# ProDoc_OHPP_003A_MIDI_B.net
KiCad netlist of a schematic drawn in EasyEDA Pro
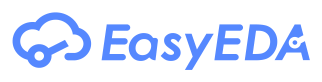
[diagram p0: POWER BLOCK DIAGRAM]
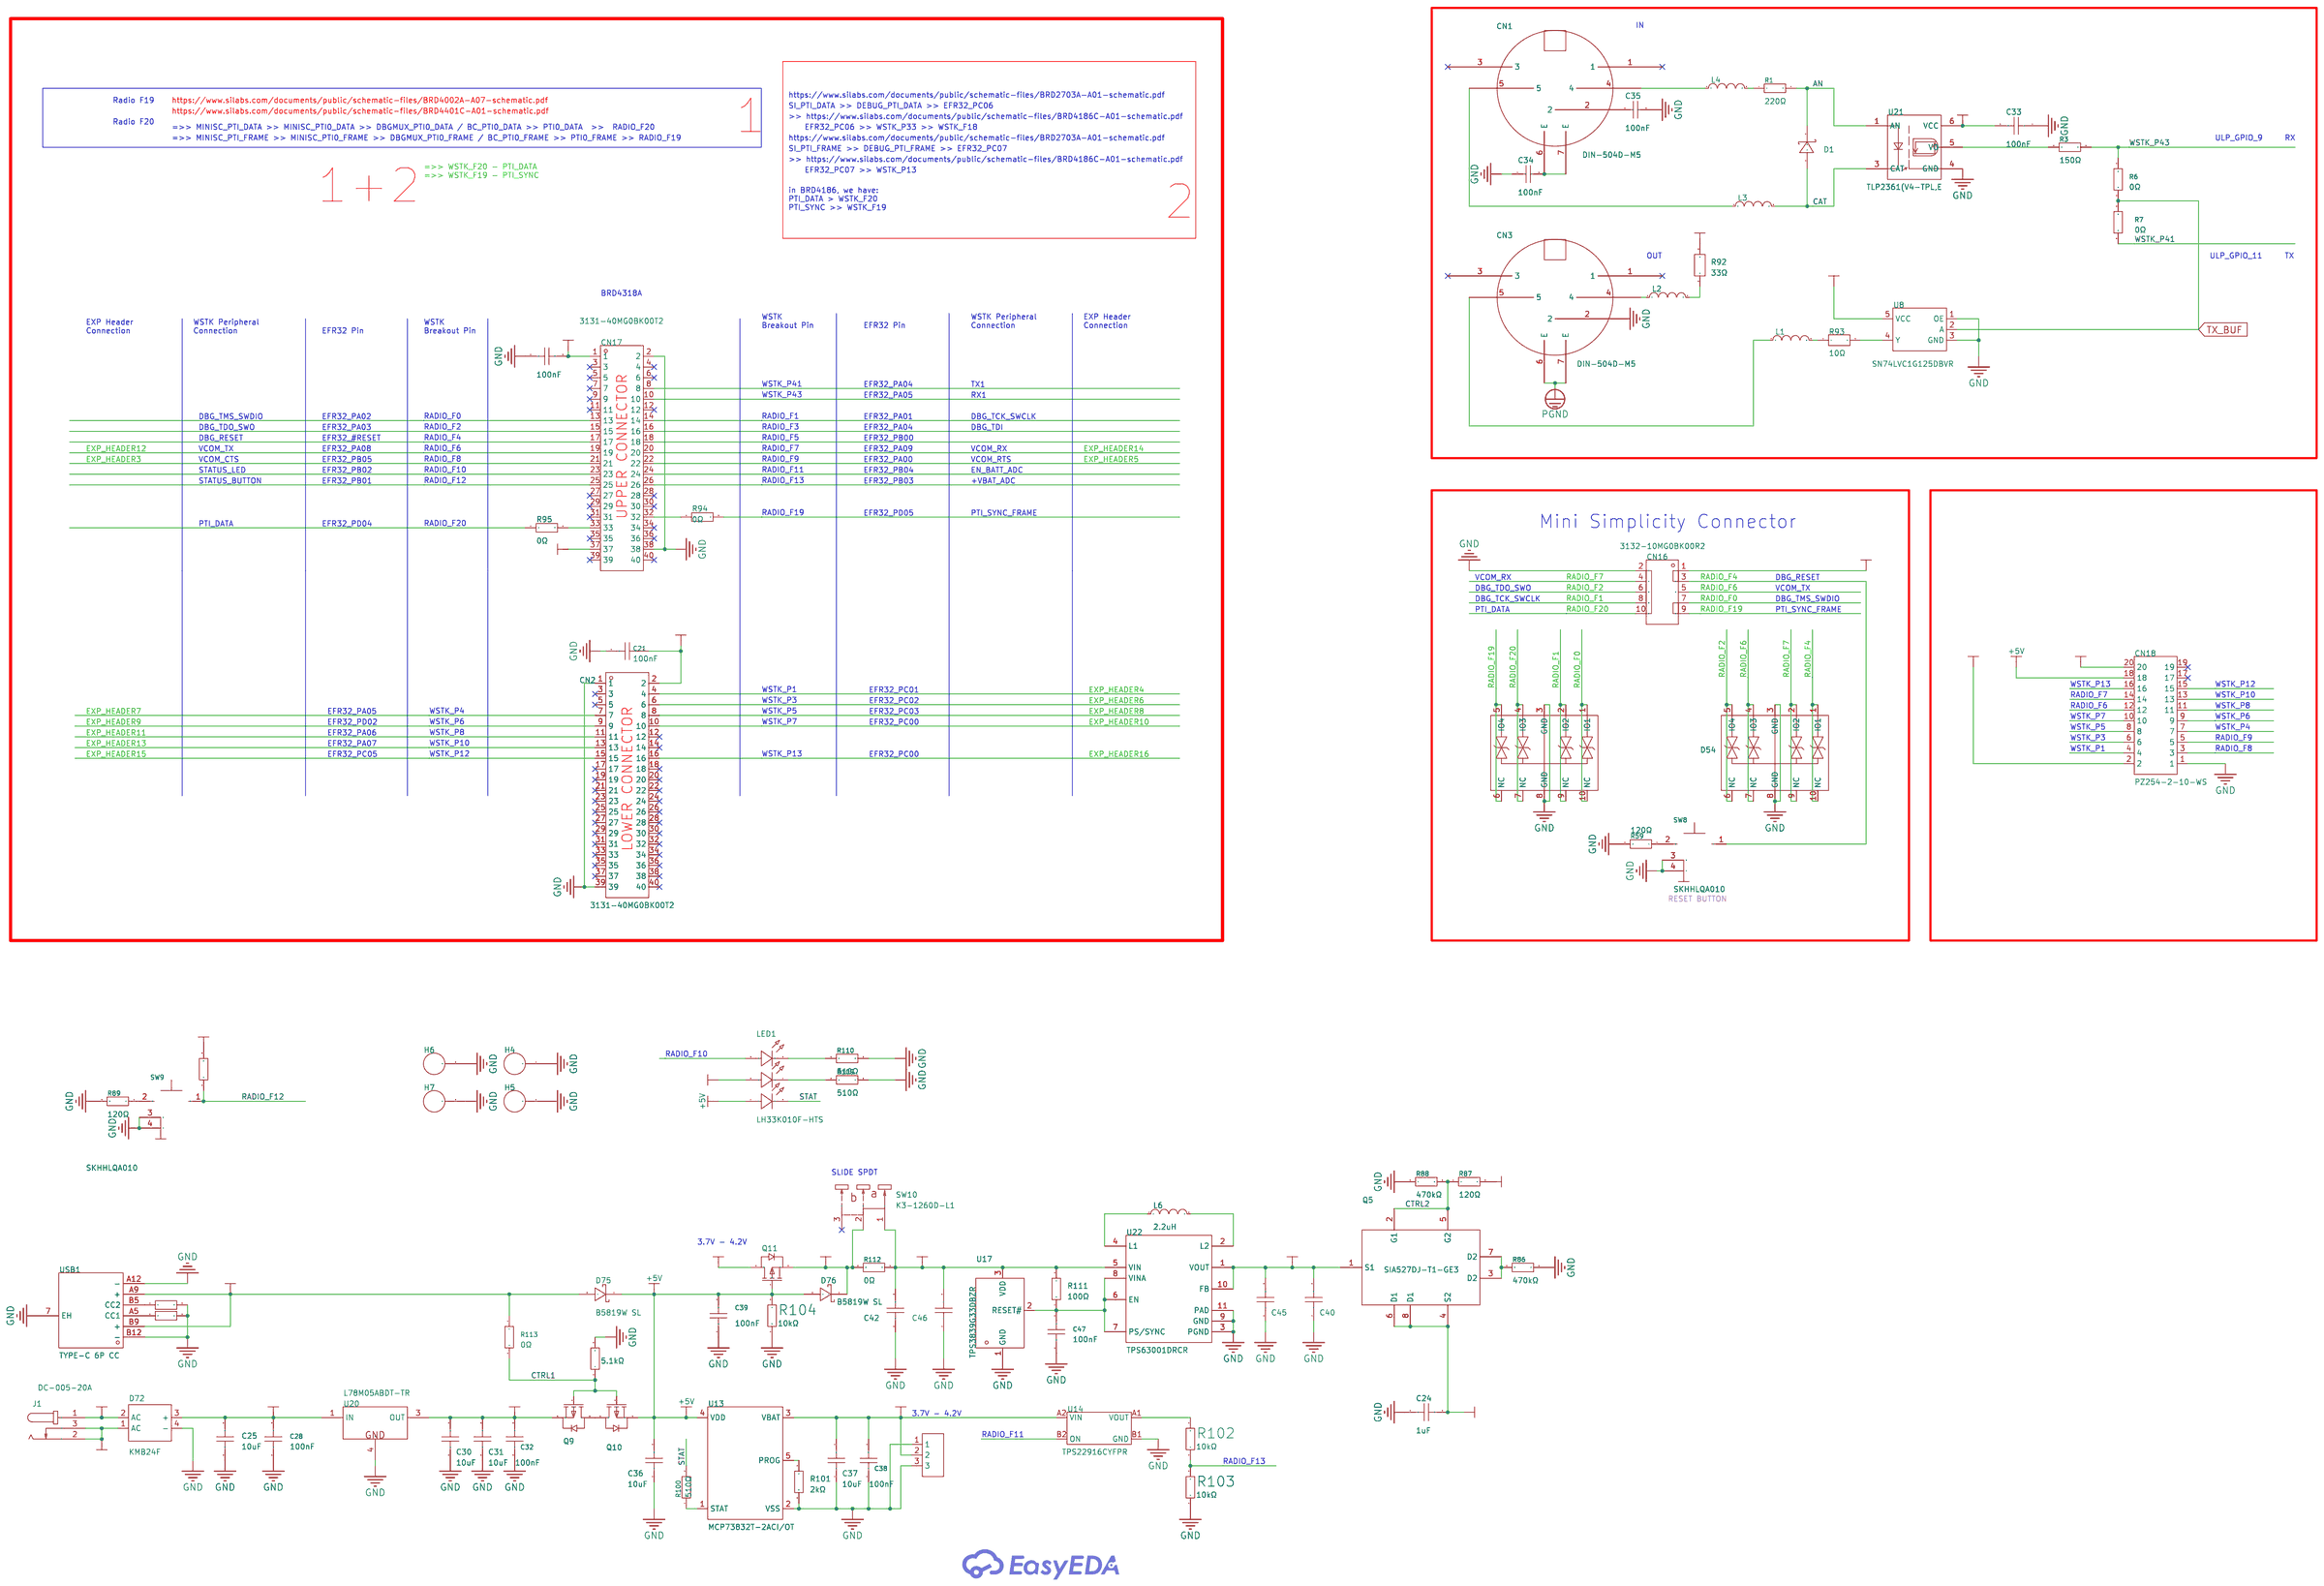
[diagram p1: MIDI]

(export (version "E")
  (design (tool "Eeschema 10.0.6"))
  (components
    (comp (ref "C20")
      (value "100nF")
      (footprint "easyedapro:C0603")
      (fields
        (field (name "Manufacturer Part") "CC0603KRX7R9BB104")
        (field (name "Manufacturer") "YAGEO(国巨)")
      )
      (libsource (lib "easyedapro") (part "CC0603KRX7R9BB104"))
    )
    (comp (ref "C21")
      (value "100nF")
      (footprint "easyedapro:C0603")
      (fields
        (field (name "Manufacturer Part") "CC0603KRX7R9BB104")
        (field (name "Manufacturer") "YAGEO(国巨)")
      )
      (libsource (lib "easyedapro") (part "CC0603KRX7R9BB104"))
    )
    (comp (ref "C24")
      (value "1uF")
      (footprint "easyedapro:C0603")
      (fields
        (field (name "Manufacturer Part") "CL10A105KB8NNNC")
        (field (name "Manufacturer") "SAMSUNG(三星)")
      )
      (libsource (lib "easyedapro") (part "CL10A105KB8NNNC"))
    )
    (comp (ref "C25")
      (value "10uF")
      (description "Capacitance:10uF Tolerance:±20% Tolerance:±20% Voltage Rating:25V Temperature Coefficient:X5R")
      (fields
        (field (name "Manufacturer Part") "CL10A106MA8NRNC")
        (field (name "Manufacturer") "SAMSUNG(三星)")
      )
      (libsource (lib "easyedapro") (part "CL21A106KAYNNNE"))
    )
    (comp (ref "C28")
      (value "100nF")
      (footprint "easyedapro:C0603")
      (fields
        (field (name "Manufacturer Part") "CC0603KRX7R9BB104")
        (field (name "Manufacturer") "YAGEO(国巨)")
      )
      (libsource (lib "easyedapro") (part "CC0603KRX7R9BB104"))
    )
    (comp (ref "C30")
      (value "10uF")
      (description "Capacitance:10uF Tolerance:±20% Tolerance:±20% Voltage Rating:25V Temperature Coefficient:X5R")
      (fields
        (field (name "Manufacturer Part") "CL10A106MA8NRNC")
        (field (name "Manufacturer") "SAMSUNG(三星)")
      )
      (libsource (lib "easyedapro") (part "CL21A106KAYNNNE"))
    )
    (comp (ref "C31")
      (value "10uF")
      (description "Capacitance:10uF Tolerance:±20% Tolerance:±20% Voltage Rating:25V Temperature Coefficient:X5R")
      (fields
        (field (name "Manufacturer Part") "CL10A106MA8NRNC")
        (field (name "Manufacturer") "SAMSUNG(三星)")
      )
      (libsource (lib "easyedapro") (part "CL21A106KAYNNNE"))
    )
    (comp (ref "C32")
      (value "100nF")
      (footprint "easyedapro:C0603")
      (fields
        (field (name "Manufacturer Part") "CC0603KRX7R9BB104")
        (field (name "Manufacturer") "YAGEO(国巨)")
      )
      (libsource (lib "easyedapro") (part "CC0603KRX7R9BB104"))
    )
    (comp (ref "C33")
      (value "100nF")
      (footprint "easyedapro:C0603")
      (fields
        (field (name "Manufacturer Part") "CC0603KRX7R9BB104")
        (field (name "Manufacturer") "YAGEO(国巨)")
      )
      (libsource (lib "easyedapro") (part "CC0603KRX7R9BB104"))
    )
    (comp (ref "C34")
      (value "100nF")
      (footprint "easyedapro:C0805")
      (fields
        (field (name "Manufacturer Part") "CL21B104KCFNNNE")
        (field (name "Manufacturer") "SAMSUNG(三星)")
      )
      (libsource (lib "easyedapro") (part "CL21B104KCFNNNE"))
    )
    (comp (ref "C35")
      (value "100nF")
      (footprint "easyedapro:C0805")
      (fields
        (field (name "Manufacturer Part") "CL21B104KCFNNNE")
        (field (name "Manufacturer") "SAMSUNG(三星)")
      )
      (libsource (lib "easyedapro") (part "CL21B104KCFNNNE"))
    )
    (comp (ref "C36")
      (value "10uF")
      (description "Capacitance:10uF Tolerance:±20% Tolerance:±20% Voltage Rating:25V Temperature Coefficient:X5R")
      (fields
        (field (name "Manufacturer Part") "CL10A106MA8NRNC")
        (field (name "Manufacturer") "SAMSUNG(三星)")
      )
      (libsource (lib "easyedapro") (part "CL21A106KAYNNNE"))
    )
    (comp (ref "C37")
      (value "10uF")
      (description "Capacitance:10uF Tolerance:±20% Tolerance:±20% Voltage Rating:25V Temperature Coefficient:X5R")
      (fields
        (field (name "Manufacturer Part") "CL10A106MA8NRNC")
        (field (name "Manufacturer") "SAMSUNG(三星)")
      )
      (libsource (lib "easyedapro") (part "CL21A106KAYNNNE"))
    )
    (comp (ref "C38")
      (value "100nF")
      (footprint "easyedapro:C0603")
      (fields
        (field (name "Manufacturer Part") "CC0603KRX7R9BB104")
        (field (name "Manufacturer") "YAGEO(国巨)")
      )
      (libsource (lib "easyedapro") (part "CC0603KRX7R9BB104"))
    )
    (comp (ref "C39")
      (value "100nF")
      (footprint "easyedapro:C0603")
      (fields
        (field (name "Manufacturer Part") "CC0603KRX7R9BB104")
        (field (name "Manufacturer") "YAGEO(国巨)")
      )
      (libsource (lib "easyedapro") (part "CC0603KRX7R9BB104"))
    )
    (comp (ref "C40")
      (value "10uF")
      (footprint "easyedapro:C0603")
      (description "Capacitance:10uF Tolerance:±20% Tolerance:±20% Voltage Rating:25V Temperature Coefficient:X5R")
      (fields
        (field (name "Manufacturer Part") "CL10A106MA8NRNC")
        (field (name "Manufacturer") "SAMSUNG(三星)")
      )
      (libsource (lib "easyedapro") (part "CL10A106MA8NRNC"))
    )
    (comp (ref "C42")
      (value "10uF")
      (footprint "easyedapro:C0603")
      (description "Capacitance:10uF Tolerance:±20% Tolerance:±20% Voltage Rating:25V Temperature Coefficient:X5R")
      (fields
        (field (name "Manufacturer Part") "CL10A106MA8NRNC")
        (field (name "Manufacturer") "SAMSUNG(三星)")
      )
      (libsource (lib "easyedapro") (part "CL10A106MA8NRNC"))
    )
    (comp (ref "C45")
      (value "10uF")
      (footprint "easyedapro:C0603")
      (description "Capacitance:10uF Tolerance:±20% Tolerance:±20% Voltage Rating:25V Temperature Coefficient:X5R")
      (fields
        (field (name "Manufacturer Part") "CL10A106MA8NRNC")
        (field (name "Manufacturer") "SAMSUNG(三星)")
      )
      (libsource (lib "easyedapro") (part "CL10A106MA8NRNC"))
    )
    (comp (ref "C46")
      (value "10uF")
      (footprint "easyedapro:C0603")
      (description "Capacitance:10uF Tolerance:±20% Tolerance:±20% Voltage Rating:25V Temperature Coefficient:X5R")
      (fields
        (field (name "Manufacturer Part") "CL10A106MA8NRNC")
        (field (name "Manufacturer") "SAMSUNG(三星)")
      )
      (libsource (lib "easyedapro") (part "CL10A106MA8NRNC"))
    )
    (comp (ref "C47")
      (value "100nF")
      (footprint "easyedapro:C0603")
      (fields
        (field (name "Manufacturer Part") "CC0603KRX7R9BB104")
        (field (name "Manufacturer") "YAGEO(国巨)")
      )
      (libsource (lib "easyedapro") (part "CC0603KRX7R9BB104"))
    )
    (comp (ref "CN1")
      (value "DIN-504D-M5")
      (footprint "easyedapro:CONN-TH_DIN-504D-M5")
      (fields (field (name "Manufacturer") "HOOYA(皓宇电子)"))
      (libsource (lib "easyedapro") (part "DIN-504D-M5-CP-V1.0.0"))
    )
    (comp (ref "CN2")
      (value "3131-40MG0BK00T2")
      (footprint "easyedapro:CONN-SMD_40P-P1.27_WCON_3131-40MG0BK00T2")
      (fields (field (name "Manufacturer") "Wcon(维峰电子)"))
      (libsource (lib "easyedapro") (part "3131-40MG0BK00T2"))
    )
    (comp (ref "CN3")
      (value "DIN-504D-M5")
      (footprint "easyedapro:CONN-TH_DIN-504D-M5")
      (fields (field (name "Manufacturer") "HOOYA(皓宇电子)"))
      (libsource (lib "easyedapro") (part "DIN-504D-M5-CP-V1.0.0"))
    )
    (comp (ref "CN16")
      (value "3132-10MG0BK00R2")
      (footprint "easyedapro:IDC-SMD_3132-10MG0BK00R2")
      (fields (field (name "Manufacturer") "Wcon(维峰电子)"))
      (libsource (lib "easyedapro") (part "3132-10MG0BK00R2"))
    )
    (comp (ref "CN17")
      (value "3131-40MG0BK00T2")
      (footprint "easyedapro:CONN-SMD_40P-P1.27_WCON_3131-40MG0BK00T2")
      (fields (field (name "Manufacturer") "Wcon(维峰电子)"))
      (libsource (lib "easyedapro") (part "3131-40MG0BK00T2-UP-CP-V1.0.0"))
    )
    (comp (ref "CN18")
      (value "PZ254-2-10-WS")
      (footprint "easyedapro:HDR-SMD_20P-P2.54-H-M-R2-C10_L8.5")
      (fields (field (name "Manufacturer") "HCTL(华灿天禄)"))
      (libsource (lib "easyedapro") (part "PZ254-2-10-WS"))
    )
    (comp (ref "D1")
      (value "MBRA140T3G")
      (footprint "easyedapro:SMA_L4.3-W2.6-LS5.2-RD")
      (fields (field (name "Manufacturer") "onsemi(安森美)"))
      (libsource (lib "easyedapro") (part "MBRA140T3G"))
    )
    (comp (ref "D54")
      (value "TPD4E02B04DQAR")
      (footprint "easyedapro:USON-10_L2.5-W1.0-P0.50-BL")
      (fields (field (name "Manufacturer") "TI(德州仪器)"))
      (libsource (lib "easyedapro") (part "TPD4E02B04DQAR"))
    )
    (comp (ref "D69")
      (value "TPD4E02B04DQAR")
      (footprint "easyedapro:USON-10_L2.5-W1.0-P0.50-BL")
      (fields (field (name "Manufacturer") "TI(德州仪器)"))
      (libsource (lib "easyedapro") (part "TPD4E02B04DQAR"))
    )
    (comp (ref "D72")
      (value "KMB24F")
      (footprint "easyedapro:DIO-BG-SMD_MBF-TL")
      (fields (field (name "Manufacturer") "MDD(辰达半导体)"))
      (libsource (lib "easyedapro") (part "KMB24F-CP-V1.0.0"))
    )
    (comp (ref "D75")
      (value "B5819W SL")
      (footprint "easyedapro:SOD-123_L2.7-W1.6-LS3.7-RD-1")
      (fields (field (name "Manufacturer") "CJ(江苏长电/长晶)"))
      (libsource (lib "easyedapro") (part "B5819W_C8598"))
    )
    (comp (ref "D76")
      (value "B5819W SL")
      (footprint "easyedapro:SOD-123_L2.7-W1.6-LS3.7-RD-1")
      (fields (field (name "Manufacturer") "CJ(江苏长电/长晶)"))
      (libsource (lib "easyedapro") (part "B5819W_C8598"))
    )
    (comp (ref "H4")
      (value "~")
      (footprint "easyedapro:HOLE_D3M5_D7M0_PAD_PTH")
      (libsource (lib "easyedapro") (part "HOLE_D3M5_D7M0_PAD_PTH"))
    )
    (comp (ref "H5")
      (value "~")
      (footprint "easyedapro:HOLE_D3M5_D7M0_PAD_PTH")
      (libsource (lib "easyedapro") (part "HOLE_D3M5_D7M0_PAD_PTH"))
    )
    (comp (ref "H6")
      (value "~")
      (footprint "easyedapro:HOLE_D3M5_D7M0_PAD_PTH")
      (libsource (lib "easyedapro") (part "HOLE_D3M5_D7M0_PAD_PTH"))
    )
    (comp (ref "H7")
      (value "~")
      (footprint "easyedapro:HOLE_D3M5_D7M0_PAD_PTH")
      (libsource (lib "easyedapro") (part "HOLE_D3M5_D7M0_PAD_PTH"))
    )
    (comp (ref "H8")
      (value "KH-2.54PH180-1X3P-L11.5")
      (footprint "easyedapro:HDR-TH_3P-P2.54-V-M")
      (fields (field (name "Manufacturer") "kinghelm(金航标)"))
      (libsource (lib "easyedapro") (part "KH-2.54PH180-1X3P-L11.5"))
    )
    (comp (ref "J1")
      (value "DC-005-20A")
      (footprint "easyedapro:DC-IN-TH_DC-005-20A")
      (fields (field (name "Manufacturer") "韩国韩荣"))
      (libsource (lib "easyedapro") (part "DC-005-20A_C136744"))
    )
    (comp (ref "L1")
      (value "MMZ1608Y102BTD25")
      (footprint "easyedapro:L0603")
      (fields (field (name "Manufacturer") "TDK"))
      (libsource (lib "easyedapro") (part "MMZ1608Y102BTD25"))
    )
    (comp (ref "L2")
      (value "MMZ1608Y102BTD25")
      (footprint "easyedapro:L0603")
      (fields (field (name "Manufacturer") "TDK"))
      (libsource (lib "easyedapro") (part "MMZ1608Y102BTD25"))
    )
    (comp (ref "L3")
      (value "MMZ1608Y102BTD25")
      (footprint "easyedapro:L0603")
      (fields (field (name "Manufacturer") "TDK"))
      (libsource (lib "easyedapro") (part "MMZ1608Y102BTD25"))
    )
    (comp (ref "L4")
      (value "MMZ1608Y102BTD25")
      (footprint "easyedapro:L0603")
      (fields (field (name "Manufacturer") "TDK"))
      (libsource (lib "easyedapro") (part "MMZ1608Y102BTD25"))
    )
    (comp (ref "L6")
      (value "2.2uH")
      (footprint "easyedapro:L0806")
      (fields (field (name "Manufacturer Part") "TFM201610GHM-2R2MTAA") (field (name "Manufacturer") "TDK"))
      (libsource (lib "easyedapro") (part "TFM201610GHM-2R2MTAA"))
    )
    (comp (ref "LED1")
      (value "LH33K010F-HTS")
      (footprint "easyedapro:LED-TH_6P-L11.6-W4.4-P2.54_LH33K010F-HTS")
      (description "Lamp Holder Type:-")
      (fields (field (name "Manufacturer") "PARALIGHT(光鼎)"))
      (libsource (lib "easyedapro") (part "LH33K010F-HTS"))
    )
    (comp (ref "Q5")
      (value "SIA527DJ-T1-GE3")
      (footprint "easyedapro:POWERPAK-SC-70-6_L2.0-W2.0-P0.65-BL")
      (fields (field (name "Manufacturer") "VISHAY(威世)"))
      (libsource (lib "easyedapro") (part "SIA527DJ-T1-GE3-CP-V1.0.0"))
    )
    (comp (ref "Q9")
      (value "SI2301CDS-T1-GE3")
      (footprint "easyedapro:SOT-23-3_L3.0-W1.7-P0.95-LS2.9-BR")
      (fields (field (name "Manufacturer") "VISHAY(威世)"))
      (libsource (lib "easyedapro") (part "SI2301CDS-T1-GE3"))
    )
    (comp (ref "Q10")
      (value "SI2301CDS-T1-GE3")
      (footprint "easyedapro:SOT-23-3_L3.0-W1.7-P0.95-LS2.9-BR")
      (fields (field (name "Manufacturer") "VISHAY(威世)"))
      (libsource (lib "easyedapro") (part "SI2301CDS-T1-GE3"))
    )
    (comp (ref "Q11")
      (value "SI2301CDS-T1-GE3")
      (footprint "easyedapro:SOT-23-3_L3.0-W1.7-P0.95-LS2.9-BR")
      (fields (field (name "Manufacturer") "VISHAY(威世)"))
      (libsource (lib "easyedapro") (part "SI2301CDS-T1-GE3"))
    )
    (comp (ref "R1")
      (value "220Ω")
      (footprint "easyedapro:R0603")
      (fields
        (field (name "Manufacturer Part") "0603WAF2200T5E")
        (field (name "Manufacturer") "UNI-ROYAL(厚声)")
      )
      (libsource (lib "easyedapro") (part "0603WAF2200T5E"))
    )
    (comp (ref "R3")
      (value "150Ω")
      (footprint "easyedapro:R0603")
      (fields
        (field (name "Manufacturer Part") "0603WAF1500T5E")
        (field (name "Manufacturer") "UNI-ROYAL(厚声)")
      )
      (libsource (lib "easyedapro") (part "0603WAF1500T5E"))
    )
    (comp (ref "R6")
      (value "0Ω")
      (footprint "easyedapro:R0402")
      (fields
        (field (name "Manufacturer Part") "0402WGF0000TCE")
        (field (name "Manufacturer") "UNI-ROYAL(厚声)")
      )
      (libsource (lib "easyedapro") (part "0402WGF0000TCE"))
    )
    (comp (ref "R7")
      (value "0Ω")
      (footprint "easyedapro:R0402")
      (fields
        (field (name "Manufacturer Part") "0402WGF0000TCE")
        (field (name "Manufacturer") "UNI-ROYAL(厚声)")
      )
      (libsource (lib "easyedapro") (part "0402WGF0000TCE"))
    )
    (comp (ref "R59")
      (value "120Ω")
      (footprint "easyedapro:R0603")
      (fields
        (field (name "Manufacturer Part") "0603WAF1200T5E")
        (field (name "Manufacturer") "UNI-ROYAL(厚声)")
      )
      (libsource (lib "easyedapro") (part "0603WAF1200T5E"))
    )
    (comp (ref "R86")
      (value "470kΩ")
      (footprint "easyedapro:R0603")
      (fields
        (field (name "Manufacturer Part") "0603WAF4703T5E")
        (field (name "Manufacturer") "UNI-ROYAL(厚声)")
      )
      (libsource (lib "easyedapro") (part "0603WAF4703T5E"))
    )
    (comp (ref "R87")
      (value "120Ω")
      (footprint "easyedapro:R0603")
      (fields
        (field (name "Manufacturer Part") "0603WAF1200T5E")
        (field (name "Manufacturer") "UNI-ROYAL(厚声)")
      )
      (libsource (lib "easyedapro") (part "0603WAF1200T5E"))
    )
    (comp (ref "R88")
      (value "470kΩ")
      (footprint "easyedapro:R0603")
      (fields
        (field (name "Manufacturer Part") "0603WAF4703T5E")
        (field (name "Manufacturer") "UNI-ROYAL(厚声)")
      )
      (libsource (lib "easyedapro") (part "0603WAF4703T5E"))
    )
    (comp (ref "R89")
      (value "120Ω")
      (footprint "easyedapro:R0603")
      (fields
        (field (name "Manufacturer Part") "0603WAF1200T5E")
        (field (name "Manufacturer") "UNI-ROYAL(厚声)")
      )
      (libsource (lib "easyedapro") (part "0603WAF1200T5E"))
    )
    (comp (ref "R91")
      (value "10kΩ")
      (footprint "easyedapro:R0603")
      (fields
        (field (name "Manufacturer Part") "0603WAF1002T5E")
        (field (name "Manufacturer") "UNI-ROYAL(厚声)")
      )
      (libsource (lib "easyedapro") (part "0603WAF1002T5E"))
    )
    (comp (ref "R92")
      (value "33Ω")
      (fields
        (field (name "Manufacturer Part") "AS05W2J0330T5E")
        (field (name "Manufacturer") "UNI-ROYAL(厚声)")
      )
      (libsource (lib "easyedapro") (part "CRCW080533R0FKEAHP"))
    )
    (comp (ref "R93")
      (value "10Ω")
      (footprint "easyedapro:R0805")
      (fields (field (name "Manufacturer Part") "AC0805FR-7W10RL") (field (name "Manufacturer") "YAGEO(国巨)"))
      (libsource (lib "easyedapro") (part "AC0805FR-7W10RL"))
    )
    (comp (ref "R94")
      (value "0Ω")
      (footprint "easyedapro:R0603")
      (fields
        (field (name "Manufacturer Part") "0603WAF0000T5E")
        (field (name "Manufacturer") "UNI-ROYAL(厚声)")
      )
      (libsource (lib "easyedapro") (part "0603WAF0000T5E"))
    )
    (comp (ref "R95")
      (value "0Ω")
      (footprint "easyedapro:R0603")
      (fields
        (field (name "Manufacturer Part") "0603WAF0000T5E")
        (field (name "Manufacturer") "UNI-ROYAL(厚声)")
      )
      (libsource (lib "easyedapro") (part "0603WAF0000T5E"))
    )
    (comp (ref "R96")
      (value "5.1kΩ")
      (fields
        (field (name "Manufacturer Part") "0603WAF5101T5E")
        (field (name "Manufacturer") "UNI-ROYAL(厚声)")
      )
      (libsource (lib "easyedapro") (part "0402WGF5101TCE"))
    )
    (comp (ref "R97")
      (value "5.1kΩ")
      (fields
        (field (name "Manufacturer Part") "0603WAF5101T5E")
        (field (name "Manufacturer") "UNI-ROYAL(厚声)")
      )
      (libsource (lib "easyedapro") (part "0402WGF5101TCE"))
    )
    (comp (ref "R98")
      (value "5.1kΩ")
      (fields
        (field (name "Manufacturer Part") "0603WAF5101T5E")
        (field (name "Manufacturer") "UNI-ROYAL(厚声)")
      )
      (libsource (lib "easyedapro") (part "0402WGF5101TCE"))
    )
    (comp (ref "R100")
      (value "510Ω")
      (footprint "easyedapro:R0603")
      (fields
        (field (name "Manufacturer Part") "0603WAF5100T5E")
        (field (name "Manufacturer") "UNI-ROYAL(厚声)")
      )
      (libsource (lib "easyedapro") (part "0603WAF5100T5E"))
    )
    (comp (ref "R101")
      (value "2kΩ")
      (footprint "easyedapro:R0603")
      (fields
        (field (name "Manufacturer Part") "0603WAF2001T5E")
        (field (name "Manufacturer") "UNI-ROYAL(厚声)")
      )
      (libsource (lib "easyedapro") (part "0603WAF2001T5E"))
    )
    (comp (ref "R102")
      (value "10kΩ")
      (footprint "easyedapro:R0603")
      (fields
        (field (name "Manufacturer Part") "0603WAF1002T5E")
        (field (name "Manufacturer") "UNI-ROYAL(厚声)")
      )
      (libsource (lib "easyedapro") (part "0603WAF1002T5E"))
    )
    (comp (ref "R103")
      (value "10kΩ")
      (footprint "easyedapro:R0603")
      (fields
        (field (name "Manufacturer Part") "0603WAF1002T5E")
        (field (name "Manufacturer") "UNI-ROYAL(厚声)")
      )
      (libsource (lib "easyedapro") (part "0603WAF1002T5E"))
    )
    (comp (ref "R104")
      (value "10kΩ")
      (footprint "easyedapro:R0603")
      (fields
        (field (name "Manufacturer Part") "0603WAF1002T5E")
        (field (name "Manufacturer") "UNI-ROYAL(厚声)")
      )
      (libsource (lib "easyedapro") (part "0603WAF1002T5E"))
    )
    (comp (ref "R109")
      (value "510Ω")
      (footprint "easyedapro:R0603")
      (fields
        (field (name "Manufacturer Part") "0603WAF5100T5E")
        (field (name "Manufacturer") "UNI-ROYAL(厚声)")
      )
      (libsource (lib "easyedapro") (part "0603WAF5100T5E"))
    )
    (comp (ref "R110")
      (value "510Ω")
      (footprint "easyedapro:R0603")
      (fields
        (field (name "Manufacturer Part") "0603WAF5100T5E")
        (field (name "Manufacturer") "UNI-ROYAL(厚声)")
      )
      (libsource (lib "easyedapro") (part "0603WAF5100T5E"))
    )
    (comp (ref "R111")
      (value "100Ω")
      (footprint "easyedapro:R0603")
      (fields
        (field (name "Manufacturer Part") "0603WAF1000T5E")
        (field (name "Manufacturer") "UNI-ROYAL(厚声)")
      )
      (libsource (lib "easyedapro") (part "0603WAF1000T5E"))
    )
    (comp (ref "R112")
      (value "0Ω")
      (footprint "easyedapro:R0402")
      (fields
        (field (name "Manufacturer Part") "0402WGF0000TCE")
        (field (name "Manufacturer") "UNI-ROYAL(厚声)")
      )
      (libsource (lib "easyedapro") (part "0402WGF0000TCE"))
    )
    (comp (ref "R113")
      (value "0Ω")
      (footprint "easyedapro:R0402")
      (fields
        (field (name "Manufacturer Part") "0402WGF0000TCE")
        (field (name "Manufacturer") "UNI-ROYAL(厚声)")
      )
      (libsource (lib "easyedapro") (part "0402WGF0000TCE"))
    )
    (comp (ref "SW8")
      (value "SKHHLQA010")
      (footprint "easyedapro:KEY-TH_4P-SKHHLQA010")
      (fields (field (name "Manufacturer") "ALPSALPINE(阿尔卑斯阿尔派)"))
      (libsource (lib "easyedapro") (part "SKHHLQA010"))
    )
    (comp (ref "SW9")
      (value "SKHHLQA010")
      (footprint "easyedapro:KEY-TH_4P-SKHHLQA010")
      (fields (field (name "Manufacturer") "ALPSALPINE(阿尔卑斯阿尔派)"))
      (libsource (lib "easyedapro") (part "SKHHLQA010"))
    )
    (comp (ref "SW10")
      (value "K3-1260D-L1")
      (footprint "easyedapro:SW-TH_K3-1260D-L1")
      (fields (field (name "Manufacturer") "韩国韩荣"))
      (libsource (lib "easyedapro") (part "K3-1260D-L1"))
    )
    (comp (ref "U8")
      (value "SN74LVC1G125DBVR")
      (footprint "easyedapro:SOT-23-5_L3.0-W1.7-P0.95-LS2.8-BL")
      (fields (field (name "Manufacturer") "TI(德州仪器)"))
      (libsource (lib "easyedapro") (part "SN74LVC1G125DBVR-CP-V1.0.0"))
    )
    (comp (ref "U13")
      (value "MCP73832T-2ACI/OT")
      (footprint "easyedapro:SOT-23-5_L3.0-W1.7-P0.95-LS2.8-BR")
      (fields (field (name "Manufacturer") "MICROCHIP(美国微芯)"))
      (libsource (lib "easyedapro") (part "MCP73832T-2ACI/OT_CP_V1.0.0"))
    )
    (comp (ref "U14")
      (value "TPS22916CYFPR")
      (footprint "easyedapro:DSBGA-4_L0.8-W0.8-R2-C2-P0.40-BL")
      (fields (field (name "Manufacturer") "TI(德州仪器)"))
      (libsource (lib "easyedapro") (part "TPS22916CYFPR"))
    )
    (comp (ref "U17")
      (value "TPS3839G33DBZR")
      (footprint "easyedapro:SOT-23-3_L2.9-W1.3-P1.90-LS2.4-BR")
      (fields (field (name "Manufacturer") "TI(德州仪器)"))
      (libsource (lib "easyedapro") (part "TPS3839G33DBZR_CP_v1.0.0"))
    )
    (comp (ref "U20")
      (value "L78M05ABDT-TR")
      (footprint "easyedapro:TO-252-2_L6.5-W6.1-P4.58-LS10.0-TL")
      (fields (field (name "Manufacturer") "ST(意法半导体)"))
      (libsource (lib "easyedapro") (part "L78M05ABDT-TR"))
    )
    (comp (ref "U21")
      (value "TLP2361(V4-TPL,E")
      (footprint "easyedapro:OPTO-SMD-5_L3.7-W4.6-P1.27-LS7.0-BR")
      (fields (field (name "Manufacturer") "TOSHIBA(东芝)"))
      (libsource (lib "easyedapro") (part "TLP2361(V4-TPL,E"))
    )
    (comp (ref "U22")
      (value "TPS63001DRCR")
      (footprint "easyedapro:VSON-10_L3.0-W3.0-P0.50-TL-EP_TPS62410DRCR")
      (fields (field (name "Manufacturer") "TI(德州仪器)"))
      (libsource (lib "easyedapro") (part "TPS63001DRCR"))
    )
    (comp (ref "USB1")
      (value "TYPE-C 6P CC")
      (footprint "easyedapro:TYPE-C-TH_SHOUHAN_TYPE-C-6P-CC")
      (fields (field (name "Manufacturer") "SHOU HAN(首韩)"))
      (libsource (lib "easyedapro") (part "TYPE-C 6P CC"))
    )
  )
  (nets
    (net (code "1") (name "+3.3V_EFR") (class "Default")
      (node (ref "C20") (pin "2") (pinfunction "2_2") (pintype "unspecified"))
      (node (ref "C21") (pin "2") (pinfunction "2_2") (pintype "unspecified"))
      (node (ref "C24") (pin "2") (pinfunction "2_2") (pintype "unspecified"))
      (node (ref "C33") (pin "2") (pinfunction "2_2") (pintype "unspecified"))
      (node (ref "CN16") (pin "1") (pinfunction "1_1") (pintype "input"))
      (node (ref "CN17") (pin "1") (pinfunction "1_1") (pintype "unspecified"))
      (node (ref "CN18") (pin "2") (pinfunction "2_2") (pintype "unspecified"))
      (node (ref "CN2") (pin "2") (pinfunction "2_2") (pintype "unspecified"))
      (node (ref "LED1") (pin "3") (pinfunction "A_3") (pintype "unspecified"))
      (node (ref "Q5") (pin "4") (pinfunction "S2_4") (pintype "unspecified"))
      (node (ref "Q5") (pin "6") (pinfunction "D1_6") (pintype "unspecified"))
      (node (ref "Q5") (pin "8") (pinfunction "D1_8") (pintype "unspecified"))
      (node (ref "R91") (pin "2") (pinfunction "2_2") (pintype "input"))
      (node (ref "R92") (pin "2") (pinfunction "2_2") (pintype "unspecified"))
      (node (ref "U21") (pin "6") (pinfunction "VCC_6") (pintype "unspecified"))
      (node (ref "U8") (pin "5") (pinfunction "VCC_5") (pintype "unspecified"))
    )
    (net (code "2") (name "+3V3_BUCK_BOOST") (class "Default")
      (node (ref "C40") (pin "2") (pinfunction "2_2") (pintype "input"))
      (node (ref "C45") (pin "2") (pinfunction "2_2") (pintype "input"))
      (node (ref "CN18") (pin "20") (pinfunction "20_20") (pintype "unspecified"))
      (node (ref "Q5") (pin "1") (pinfunction "S1_1") (pintype "unspecified"))
      (node (ref "U22") (pin "1") (pinfunction "VOUT_1") (pintype "unspecified"))
      (node (ref "U22") (pin "10") (pinfunction "FB_10") (pintype "unspecified"))
    )
    (net (code "3") (name "+5V") (class "Default")
      (node (ref "C36") (pin "2") (pinfunction "2_2") (pintype "unspecified"))
      (node (ref "C39") (pin "2") (pinfunction "2_2") (pintype "unspecified"))
      (node (ref "CN17") (pin "37") (pinfunction "37_37") (pintype "unspecified"))
      (node (ref "CN18") (pin "18") (pinfunction "18_18") (pintype "unspecified"))
      (node (ref "D75") (pin "1") (pinfunction "-_1") (pintype "unspecified"))
      (node (ref "D76") (pin "2") (pinfunction "+_2") (pintype "unspecified"))
      (node (ref "LED1") (pin "1") (pinfunction "A_1") (pintype "unspecified"))
      (node (ref "Q10") (pin "2") (pinfunction "S_2") (pintype "unspecified"))
      (node (ref "Q11") (pin "1") (pinfunction "G_1") (pintype "unspecified"))
      (node (ref "R104") (pin "2") (pinfunction "2_2") (pintype "input"))
      (node (ref "U13") (pin "4") (pinfunction "VDD_4") (pintype "unspecified"))
    )
    (net (code "4") (name "+5V_1") (class "Default")
      (node (ref "C30") (pin "2") (pinfunction "2_2") (pintype "unspecified"))
      (node (ref "C31") (pin "2") (pinfunction "2_2") (pintype "unspecified"))
      (node (ref "C32") (pin "2") (pinfunction "2_2") (pintype "unspecified"))
      (node (ref "Q9") (pin "2") (pinfunction "S_2") (pintype "unspecified"))
      (node (ref "U20") (pin "3") (pinfunction "OUT_3") (pintype "unspecified"))
    )
    (net (code "5") (name "+5V_2") (class "Default")
      (node (ref "D75") (pin "2") (pinfunction "+_2") (pintype "unspecified"))
      (node (ref "R113") (pin "1") (pinfunction "1_1") (pintype "input"))
      (node (ref "USB1") (pin "A9") (pinfunction "+_A9") (pintype "unspecified"))
      (node (ref "USB1") (pin "B9") (pinfunction "+_B9") (pintype "unspecified"))
    )
    (net (code "6") (name "+8.3V") (class "Default")
      (node (ref "C25") (pin "2") (pinfunction "2_2") (pintype "unspecified"))
      (node (ref "C28") (pin "2") (pinfunction "2_2") (pintype "unspecified"))
      (node (ref "D72") (pin "3") (pinfunction "+_3") (pintype "unspecified"))
      (node (ref "U20") (pin "1") (pinfunction "IN_1") (pintype "unspecified"))
    )
    (net (code "7") (name "+9V") (class "Default")
      (node (ref "D72") (pin "2") (pinfunction "AC_2") (pintype "unspecified"))
      (node (ref "J1") (pin "1") (pinfunction "1_1") (pintype "unspecified"))
    )
    (net (code "8") (name "+VBAT") (class "Default")
      (node (ref "C37") (pin "2") (pinfunction "2_2") (pintype "unspecified"))
      (node (ref "C38") (pin "2") (pinfunction "2_2") (pintype "unspecified"))
      (node (ref "H8") (pin "2") (pinfunction "2_2") (pintype "unspecified"))
      (node (ref "Q11") (pin "3") (pinfunction "D_3") (pintype "unspecified"))
      (node (ref "U13") (pin "3") (pinfunction "VBAT_3") (pintype "unspecified"))
      (node (ref "U14") (pin "A2") (pinfunction "VIN_A2") (pintype "input"))
    )
    (net (code "9") (name "+VCC") (class "Default")
      (node (ref "D76") (pin "1") (pinfunction "-_1") (pintype "unspecified"))
      (node (ref "Q11") (pin "2") (pinfunction "S_2") (pintype "unspecified"))
      (node (ref "R112") (pin "2") (pinfunction "2_2") (pintype "input"))
      (node (ref "SW10") (pin "2") (pinfunction "2_2") (pintype "unspecified"))
    )
    (net (code "10") (name "+VCC1") (class "Default")
      (node (ref "C42") (pin "2") (pinfunction "2_2") (pintype "input"))
      (node (ref "C46") (pin "2") (pinfunction "2_2") (pintype "input"))
      (node (ref "R111") (pin "2") (pinfunction "2_2") (pintype "input"))
      (node (ref "R112") (pin "1") (pinfunction "1_1") (pintype "input"))
      (node (ref "R87") (pin "2") (pinfunction "2_2") (pintype "input"))
      (node (ref "SW10") (pin "1") (pinfunction "1_1") (pintype "unspecified"))
      (node (ref "U17") (pin "3") (pinfunction "VDD_3") (pintype "input"))
      (node (ref "U22") (pin "5") (pinfunction "VIN_5") (pintype "unspecified"))
    )
    (net (code "11") (name "-9V") (class "Default")
      (node (ref "D72") (pin "1") (pinfunction "AC_1") (pintype "unspecified"))
      (node (ref "J1") (pin "2") (pinfunction "2_2") (pintype "unspecified"))
      (node (ref "J1") (pin "3") (pinfunction "3_3") (pintype "unspecified"))
    )
    (net (code "12") (name "AN") (class "Default")
      (node (ref "D1") (pin "1") (pinfunction "C_1") (pintype "unspecified"))
      (node (ref "R1") (pin "2") (pinfunction "2_2") (pintype "input"))
      (node (ref "U21") (pin "1") (pinfunction "AN_1") (pintype "unspecified"))
    )
    (net (code "13") (name "CAT") (class "Default")
      (node (ref "D1") (pin "2") (pinfunction "A_2") (pintype "unspecified"))
      (node (ref "L3") (pin "2") (pinfunction "2_2") (pintype "input"))
      (node (ref "U21") (pin "3") (pinfunction "CAT_3") (pintype "unspecified"))
    )
    (net (code "14") (name "CTRL1") (class "Default")
      (node (ref "Q10") (pin "1") (pinfunction "G_1") (pintype "unspecified"))
      (node (ref "Q9") (pin "1") (pinfunction "G_1") (pintype "unspecified"))
      (node (ref "R113") (pin "2") (pinfunction "2_2") (pintype "input"))
      (node (ref "R98") (pin "1") (pinfunction "1_1") (pintype "input"))
    )
    (net (code "15") (name "CTRL2") (class "Default")
      (node (ref "Q5") (pin "2") (pinfunction "G1_2") (pintype "unspecified"))
      (node (ref "Q5") (pin "5") (pinfunction "G2_5") (pintype "unspecified"))
      (node (ref "R87") (pin "1") (pinfunction "1_1") (pintype "input"))
      (node (ref "R88") (pin "2") (pinfunction "2_2") (pintype "input"))
    )
    (net (code "16") (name "GND") (class "Default")
      (node (ref "C20") (pin "1") (pinfunction "1_1") (pintype "unspecified"))
      (node (ref "C21") (pin "1") (pinfunction "1_1") (pintype "unspecified"))
      (node (ref "C24") (pin "1") (pinfunction "1_1") (pintype "unspecified"))
      (node (ref "C25") (pin "1") (pinfunction "1_1") (pintype "unspecified"))
      (node (ref "C28") (pin "1") (pinfunction "1_1") (pintype "unspecified"))
      (node (ref "C30") (pin "1") (pinfunction "1_1") (pintype "unspecified"))
      (node (ref "C31") (pin "1") (pinfunction "1_1") (pintype "unspecified"))
      (node (ref "C32") (pin "1") (pinfunction "1_1") (pintype "unspecified"))
      (node (ref "C33") (pin "1") (pinfunction "1_1") (pintype "unspecified"))
      (node (ref "C34") (pin "1") (pinfunction "1_1") (pintype "input"))
      (node (ref "C35") (pin "1") (pinfunction "1_1") (pintype "input"))
      (node (ref "C36") (pin "1") (pinfunction "1_1") (pintype "unspecified"))
      (node (ref "C37") (pin "1") (pinfunction "1_1") (pintype "unspecified"))
      (node (ref "C38") (pin "1") (pinfunction "1_1") (pintype "unspecified"))
      (node (ref "C39") (pin "1") (pinfunction "1_1") (pintype "unspecified"))
      (node (ref "C40") (pin "1") (pinfunction "1_1") (pintype "input"))
      (node (ref "C42") (pin "1") (pinfunction "1_1") (pintype "input"))
      (node (ref "C45") (pin "1") (pinfunction "1_1") (pintype "input"))
      (node (ref "C46") (pin "1") (pinfunction "1_1") (pintype "input"))
      (node (ref "C47") (pin "2") (pinfunction "2_2") (pintype "unspecified"))
      (node (ref "CN16") (pin "2") (pinfunction "2_2") (pintype "input"))
      (node (ref "CN17") (pin "2") (pinfunction "2_2") (pintype "unspecified"))
      (node (ref "CN17") (pin "38") (pinfunction "38_38") (pintype "unspecified"))
      (node (ref "CN18") (pin "1") (pinfunction "1_1") (pintype "unspecified"))
      (node (ref "CN2") (pin "1") (pinfunction "1_1") (pintype "unspecified"))
      (node (ref "CN2") (pin "39") (pinfunction "39_39") (pintype "unspecified"))
      (node (ref "CN3") (pin "2") (pinfunction "2_2") (pintype "unspecified"))
      (node (ref "D54") (pin "3") (pinfunction "GND_3") (pintype "unspecified"))
      (node (ref "D54") (pin "8") (pinfunction "GND_8") (pintype "unspecified"))
      (node (ref "D69") (pin "3") (pinfunction "GND_3") (pintype "unspecified"))
      (node (ref "D69") (pin "8") (pinfunction "GND_8") (pintype "unspecified"))
      (node (ref "D72") (pin "4") (pinfunction "-_4") (pintype "unspecified"))
      (node (ref "H4") (pin "1") (pinfunction "1_1") (pintype "input"))
      (node (ref "H5") (pin "1") (pinfunction "1_1") (pintype "input"))
      (node (ref "H6") (pin "1") (pinfunction "1_1") (pintype "input"))
      (node (ref "H7") (pin "1") (pinfunction "1_1") (pintype "input"))
      (node (ref "H8") (pin "1") (pinfunction "1_1") (pintype "unspecified"))
      (node (ref "H8") (pin "3") (pinfunction "3_3") (pintype "unspecified"))
      (node (ref "R101") (pin "2") (pinfunction "2_2") (pintype "input"))
      (node (ref "R103") (pin "1") (pinfunction "1_1") (pintype "input"))
      (node (ref "R104") (pin "1") (pinfunction "1_1") (pintype "input"))
      (node (ref "R109") (pin "1") (pinfunction "1_1") (pintype "input"))
      (node (ref "R110") (pin "1") (pinfunction "1_1") (pintype "input"))
      (node (ref "R59") (pin "2") (pinfunction "2_2") (pintype "input"))
      (node (ref "R86") (pin "1") (pinfunction "1_1") (pintype "input"))
      (node (ref "R88") (pin "1") (pinfunction "1_1") (pintype "input"))
      (node (ref "R89") (pin "2") (pinfunction "2_2") (pintype "input"))
      (node (ref "R96") (pin "2") (pinfunction "2_2") (pintype "input"))
      (node (ref "R97") (pin "2") (pinfunction "2_2") (pintype "input"))
      (node (ref "R98") (pin "2") (pinfunction "2_2") (pintype "input"))
      (node (ref "SW8") (pin "3") (pinfunction "3_3") (pintype "input"))
      (node (ref "SW8") (pin "4") (pinfunction "4_4") (pintype "input"))
      (node (ref "SW9") (pin "3") (pinfunction "3_3") (pintype "input"))
      (node (ref "SW9") (pin "4") (pinfunction "4_4") (pintype "input"))
      (node (ref "U13") (pin "2") (pinfunction "VSS_2") (pintype "unspecified"))
      (node (ref "U14") (pin "B1") (pinfunction "GND_B1") (pintype "input"))
      (node (ref "U17") (pin "1") (pinfunction "GND_1") (pintype "input"))
      (node (ref "U20") (pin "4") (pinfunction "GND_4") (pintype "unspecified"))
      (node (ref "U21") (pin "4") (pinfunction "GND_4") (pintype "unspecified"))
      (node (ref "U22") (pin "11") (pinfunction "PAD_11") (pintype "unspecified"))
      (node (ref "U22") (pin "3") (pinfunction "PGND_3") (pintype "unspecified"))
      (node (ref "U22") (pin "9") (pinfunction "GND_9") (pintype "unspecified"))
      (node (ref "U8") (pin "1") (pinfunction "OE_1") (pintype "unspecified"))
      (node (ref "U8") (pin "3") (pinfunction "GND_3") (pintype "unspecified"))
      (node (ref "USB1") (pin "7") (pinfunction "EH_7") (pintype "unspecified"))
      (node (ref "USB1") (pin "A12") (pinfunction "-_A12") (pintype "unspecified"))
      (node (ref "USB1") (pin "B12") (pinfunction "-_B12") (pintype "unspecified"))
    )
    (net (code "17") (name "Net-(C34-Pad2)") (class "Default")
      (node (ref "C34") (pin "2") (pinfunction "2_2") (pintype "input"))
      (node (ref "CN1") (pin "6") (pinfunction "E_6") (pintype "unspecified"))
      (node (ref "CN1") (pin "7") (pinfunction "E_7") (pintype "unspecified"))
    )
    (net (code "18") (name "Net-(C35-Pad2)") (class "Default")
      (node (ref "C35") (pin "2") (pinfunction "2_2") (pintype "input"))
      (node (ref "CN1") (pin "2") (pinfunction "2_2") (pintype "unspecified"))
    )
    (net (code "19") (name "Net-(CN1-Pad4)") (class "Default")
      (node (ref "CN1") (pin "4") (pinfunction "4_4") (pintype "unspecified"))
      (node (ref "L4") (pin "1") (pinfunction "1_1") (pintype "input"))
    )
    (net (code "20") (name "Net-(CN1-Pad5)") (class "Default")
      (node (ref "CN1") (pin "5") (pinfunction "5_5") (pintype "unspecified"))
      (node (ref "L3") (pin "1") (pinfunction "1_1") (pintype "input"))
    )
    (net (code "21") (name "Net-(CN3-Pad4)") (class "Default")
      (node (ref "CN3") (pin "4") (pinfunction "4_4") (pintype "unspecified"))
      (node (ref "L2") (pin "1") (pinfunction "1_1") (pintype "input"))
    )
    (net (code "22") (name "Net-(CN3-Pad5)") (class "Default")
      (node (ref "CN3") (pin "5") (pinfunction "5_5") (pintype "unspecified"))
      (node (ref "L1") (pin "1") (pinfunction "1_1") (pintype "input"))
    )
    (net (code "23") (name "Net-(CN17-Pad32)") (class "Default")
      (node (ref "CN17") (pin "32") (pinfunction "32_32") (pintype "unspecified"))
      (node (ref "R94") (pin "1") (pinfunction "1_1") (pintype "input"))
    )
    (net (code "24") (name "Net-(CN17-Pad33)") (class "Default")
      (node (ref "CN17") (pin "33") (pinfunction "33_33") (pintype "unspecified"))
      (node (ref "R95") (pin "2") (pinfunction "2_2") (pintype "input"))
    )
    (net (code "25") (name "Net-(L1-Pad2)") (class "Default")
      (node (ref "L1") (pin "2") (pinfunction "2_2") (pintype "input"))
      (node (ref "R93") (pin "1") (pinfunction "1_1") (pintype "unspecified"))
    )
    (net (code "26") (name "Net-(L2-Pad2)") (class "Default")
      (node (ref "L2") (pin "2") (pinfunction "2_2") (pintype "input"))
      (node (ref "R92") (pin "1") (pinfunction "1_1") (pintype "unspecified"))
    )
    (net (code "27") (name "Net-(L4-Pad2)") (class "Default")
      (node (ref "L4") (pin "2") (pinfunction "2_2") (pintype "input"))
      (node (ref "R1") (pin "1") (pinfunction "1_1") (pintype "input"))
    )
    (net (code "28") (name "Net-(LED1-C-Pad4)") (class "Default")
      (node (ref "LED1") (pin "4") (pinfunction "C_4") (pintype "unspecified"))
      (node (ref "R109") (pin "2") (pinfunction "2_2") (pintype "input"))
    )
    (net (code "29") (name "Net-(LED1-C-Pad6)") (class "Default")
      (node (ref "LED1") (pin "6") (pinfunction "C_6") (pintype "unspecified"))
      (node (ref "R110") (pin "2") (pinfunction "2_2") (pintype "input"))
    )
    (net (code "30") (name "Net-(Q5-D2-Pad3)") (class "Default")
      (node (ref "Q5") (pin "3") (pinfunction "D2_3") (pintype "unspecified"))
      (node (ref "Q5") (pin "7") (pinfunction "D2_7") (pintype "unspecified"))
      (node (ref "R86") (pin "2") (pinfunction "2_2") (pintype "input"))
    )
    (net (code "31") (name "Net-(Q10-D)") (class "Default")
      (node (ref "Q10") (pin "3") (pinfunction "D_3") (pintype "unspecified"))
      (node (ref "Q9") (pin "3") (pinfunction "D_3") (pintype "unspecified"))
    )
    (net (code "32") (name "Net-(R59-Pad1)") (class "Default")
      (node (ref "R59") (pin "1") (pinfunction "1_1") (pintype "input"))
      (node (ref "SW8") (pin "2") (pinfunction "2_2") (pintype "input"))
    )
    (net (code "33") (name "Net-(R89-Pad1)") (class "Default")
      (node (ref "R89") (pin "1") (pinfunction "1_1") (pintype "input"))
      (node (ref "SW9") (pin "2") (pinfunction "2_2") (pintype "input"))
    )
    (net (code "34") (name "Net-(U8-Y)") (class "Default")
      (node (ref "R93") (pin "2") (pinfunction "2_2") (pintype "unspecified"))
      (node (ref "U8") (pin "4") (pinfunction "Y_4") (pintype "unspecified"))
    )
    (net (code "35") (name "Net-(U13-PROG)") (class "Default")
      (node (ref "R101") (pin "1") (pinfunction "1_1") (pintype "input"))
      (node (ref "U13") (pin "5") (pinfunction "PROG_5") (pintype "unspecified"))
    )
    (net (code "36") (name "Net-(U13-STAT)") (class "Default")
      (node (ref "R100") (pin "1") (pinfunction "1_1") (pintype "input"))
      (node (ref "U13") (pin "1") (pinfunction "STAT_1") (pintype "unspecified"))
    )
    (net (code "37") (name "Net-(U14-VOUT)") (class "Default")
      (node (ref "R102") (pin "2") (pinfunction "2_2") (pintype "input"))
      (node (ref "U14") (pin "A1") (pinfunction "VOUT_A1") (pintype "input"))
    )
    (net (code "38") (name "Net-(U17-RESET#)") (class "Default")
      (node (ref "C47") (pin "1") (pinfunction "1_1") (pintype "unspecified"))
      (node (ref "R111") (pin "1") (pinfunction "1_1") (pintype "input"))
      (node (ref "U17") (pin "2") (pinfunction "RESET#_2") (pintype "input"))
      (node (ref "U22") (pin "6") (pinfunction "EN_6") (pintype "unspecified"))
      (node (ref "U22") (pin "7") (pinfunction "PS/SYNC_7") (pintype "unspecified"))
      (node (ref "U22") (pin "8") (pinfunction "VINA_8") (pintype "unspecified"))
    )
    (net (code "39") (name "Net-(U21-VO)") (class "Default")
      (node (ref "R3") (pin "1") (pinfunction "1_1") (pintype "input"))
      (node (ref "U21") (pin "5") (pinfunction "VO_5") (pintype "unspecified"))
    )
    (net (code "40") (name "Net-(U22-L1)") (class "Default")
      (node (ref "L6") (pin "1") (pinfunction "1_1") (pintype "input"))
      (node (ref "U22") (pin "4") (pinfunction "L1_4") (pintype "unspecified"))
    )
    (net (code "41") (name "Net-(U22-L2)") (class "Default")
      (node (ref "L6") (pin "2") (pinfunction "2_2") (pintype "input"))
      (node (ref "U22") (pin "2") (pinfunction "L2_2") (pintype "unspecified"))
    )
    (net (code "42") (name "Net-(USB1-CC1)") (class "Default")
      (node (ref "R97") (pin "1") (pinfunction "1_1") (pintype "input"))
      (node (ref "USB1") (pin "A5") (pinfunction "CC1_A5") (pintype "unspecified"))
    )
    (net (code "43") (name "Net-(USB1-CC2)") (class "Default")
      (node (ref "R96") (pin "1") (pinfunction "1_1") (pintype "input"))
      (node (ref "USB1") (pin "B5") (pinfunction "CC2_B5") (pintype "unspecified"))
    )
    (net (code "44") (name "PGND") (class "Default")
      (node (ref "CN3") (pin "6") (pinfunction "E_6") (pintype "unspecified"))
      (node (ref "CN3") (pin "7") (pinfunction "E_7") (pintype "unspecified"))
    )
    (net (code "45") (name "RADIO_F0") (class "Default")
      (node (ref "CN16") (pin "7") (pinfunction "7_7") (pintype "input"))
      (node (ref "CN17") (pin "13") (pinfunction "13_13") (pintype "unspecified"))
      (node (ref "D69") (pin "1") (pinfunction "IO1_1") (pintype "unspecified"))
      (node (ref "D69") (pin "10") (pinfunction "NC_10") (pintype "unspecified"))
    )
    (net (code "46") (name "RADIO_F1") (class "Default")
      (node (ref "CN16") (pin "8") (pinfunction "8_8") (pintype "input"))
      (node (ref "CN17") (pin "14") (pinfunction "14_14") (pintype "unspecified"))
      (node (ref "D69") (pin "2") (pinfunction "IO2_2") (pintype "unspecified"))
      (node (ref "D69") (pin "9") (pinfunction "NC_9") (pintype "unspecified"))
    )
    (net (code "47") (name "RADIO_F2") (class "Default")
      (node (ref "CN16") (pin "6") (pinfunction "6_6") (pintype "input"))
      (node (ref "CN17") (pin "15") (pinfunction "15_15") (pintype "unspecified"))
      (node (ref "D54") (pin "5") (pinfunction "IO4_5") (pintype "unspecified"))
      (node (ref "D54") (pin "6") (pinfunction "NC_6") (pintype "unspecified"))
    )
    (net (code "48") (name "RADIO_F3") (class "Default")
      (node (ref "CN17") (pin "16") (pinfunction "16_16") (pintype "unspecified"))
    )
    (net (code "49") (name "RADIO_F4") (class "Default")
      (node (ref "CN16") (pin "3") (pinfunction "3_3") (pintype "input"))
      (node (ref "CN17") (pin "17") (pinfunction "17_17") (pintype "unspecified"))
      (node (ref "D54") (pin "1") (pinfunction "IO1_1") (pintype "unspecified"))
      (node (ref "D54") (pin "10") (pinfunction "NC_10") (pintype "unspecified"))
      (node (ref "SW8") (pin "1") (pinfunction "1_1") (pintype "input"))
    )
    (net (code "50") (name "RADIO_F5") (class "Default")
      (node (ref "CN17") (pin "18") (pinfunction "18_18") (pintype "unspecified"))
    )
    (net (code "51") (name "RADIO_F6") (class "Default")
      (node (ref "CN16") (pin "5") (pinfunction "5_5") (pintype "input"))
      (node (ref "CN17") (pin "19") (pinfunction "19_19") (pintype "unspecified"))
      (node (ref "CN18") (pin "12") (pinfunction "12_12") (pintype "unspecified"))
      (node (ref "D54") (pin "4") (pinfunction "IO3_4") (pintype "unspecified"))
      (node (ref "D54") (pin "7") (pinfunction "NC_7") (pintype "unspecified"))
    )
    (net (code "52") (name "RADIO_F7") (class "Default")
      (node (ref "CN16") (pin "4") (pinfunction "4_4") (pintype "input"))
      (node (ref "CN17") (pin "20") (pinfunction "20_20") (pintype "unspecified"))
      (node (ref "CN18") (pin "14") (pinfunction "14_14") (pintype "unspecified"))
      (node (ref "D54") (pin "2") (pinfunction "IO2_2") (pintype "unspecified"))
      (node (ref "D54") (pin "9") (pinfunction "NC_9") (pintype "unspecified"))
    )
    (net (code "53") (name "RADIO_F8") (class "Default")
      (node (ref "CN17") (pin "21") (pinfunction "21_21") (pintype "unspecified"))
      (node (ref "CN18") (pin "3") (pinfunction "3_3") (pintype "unspecified"))
    )
    (net (code "54") (name "RADIO_F9") (class "Default")
      (node (ref "CN17") (pin "22") (pinfunction "22_22") (pintype "unspecified"))
      (node (ref "CN18") (pin "5") (pinfunction "5_5") (pintype "unspecified"))
    )
    (net (code "55") (name "RADIO_F10") (class "Default")
      (node (ref "CN17") (pin "23") (pinfunction "23_23") (pintype "unspecified"))
      (node (ref "LED1") (pin "5") (pinfunction "A_5") (pintype "unspecified"))
    )
    (net (code "56") (name "RADIO_F11") (class "Default")
      (node (ref "CN17") (pin "24") (pinfunction "24_24") (pintype "unspecified"))
      (node (ref "U14") (pin "B2") (pinfunction "ON_B2") (pintype "input"))
    )
    (net (code "57") (name "RADIO_F12") (class "Default")
      (node (ref "CN17") (pin "25") (pinfunction "25_25") (pintype "unspecified"))
      (node (ref "R91") (pin "1") (pinfunction "1_1") (pintype "input"))
      (node (ref "SW9") (pin "1") (pinfunction "1_1") (pintype "input"))
    )
    (net (code "58") (name "RADIO_F13") (class "Default")
      (node (ref "CN17") (pin "26") (pinfunction "26_26") (pintype "unspecified"))
      (node (ref "R102") (pin "1") (pinfunction "1_1") (pintype "input"))
      (node (ref "R103") (pin "2") (pinfunction "2_2") (pintype "input"))
    )
    (net (code "59") (name "RADIO_F19") (class "Default")
      (node (ref "CN16") (pin "9") (pinfunction "9_9") (pintype "input"))
      (node (ref "D69") (pin "5") (pinfunction "IO4_5") (pintype "unspecified"))
      (node (ref "D69") (pin "6") (pinfunction "NC_6") (pintype "unspecified"))
      (node (ref "R94") (pin "2") (pinfunction "2_2") (pintype "input"))
    )
    (net (code "60") (name "RADIO_F20") (class "Default")
      (node (ref "CN16") (pin "10") (pinfunction "10_10") (pintype "input"))
      (node (ref "D69") (pin "4") (pinfunction "IO3_4") (pintype "unspecified"))
      (node (ref "D69") (pin "7") (pinfunction "NC_7") (pintype "unspecified"))
      (node (ref "R95") (pin "1") (pinfunction "1_1") (pintype "input"))
    )
    (net (code "61") (name "STAT") (class "Default")
      (node (ref "LED1") (pin "2") (pinfunction "C_2") (pintype "unspecified"))
      (node (ref "R100") (pin "2") (pinfunction "2_2") (pintype "input"))
    )
    (net (code "62") (name "TX_BUF") (class "Default")
      (node (ref "R6") (pin "2") (pinfunction "2_2") (pintype "input"))
      (node (ref "R7") (pin "1") (pinfunction "1_1") (pintype "input"))
      (node (ref "U8") (pin "2") (pinfunction "A_2") (pintype "unspecified"))
    )
    (net (code "63") (name "WSTK_P1") (class "Default")
      (node (ref "CN18") (pin "4") (pinfunction "4_4") (pintype "unspecified"))
      (node (ref "CN2") (pin "4") (pinfunction "4_4") (pintype "unspecified"))
    )
    (net (code "64") (name "WSTK_P3") (class "Default")
      (node (ref "CN18") (pin "6") (pinfunction "6_6") (pintype "unspecified"))
      (node (ref "CN2") (pin "6") (pinfunction "6_6") (pintype "unspecified"))
    )
    (net (code "65") (name "WSTK_P4") (class "Default")
      (node (ref "CN18") (pin "7") (pinfunction "7_7") (pintype "unspecified"))
      (node (ref "CN2") (pin "7") (pinfunction "7_7") (pintype "unspecified"))
    )
    (net (code "66") (name "WSTK_P5") (class "Default")
      (node (ref "CN18") (pin "8") (pinfunction "8_8") (pintype "unspecified"))
      (node (ref "CN2") (pin "8") (pinfunction "8_8") (pintype "unspecified"))
    )
    (net (code "67") (name "WSTK_P6") (class "Default")
      (node (ref "CN18") (pin "9") (pinfunction "9_9") (pintype "unspecified"))
      (node (ref "CN2") (pin "9") (pinfunction "9_9") (pintype "unspecified"))
    )
    (net (code "68") (name "WSTK_P7") (class "Default")
      (node (ref "CN18") (pin "10") (pinfunction "10_10") (pintype "unspecified"))
      (node (ref "CN2") (pin "10") (pinfunction "10_10") (pintype "unspecified"))
    )
    (net (code "69") (name "WSTK_P8") (class "Default")
      (node (ref "CN18") (pin "11") (pinfunction "11_11") (pintype "unspecified"))
      (node (ref "CN2") (pin "11") (pinfunction "11_11") (pintype "unspecified"))
    )
    (net (code "70") (name "WSTK_P10") (class "Default")
      (node (ref "CN18") (pin "13") (pinfunction "13_13") (pintype "unspecified"))
      (node (ref "CN2") (pin "13") (pinfunction "13_13") (pintype "unspecified"))
    )
    (net (code "71") (name "WSTK_P12") (class "Default")
      (node (ref "CN18") (pin "15") (pinfunction "15_15") (pintype "unspecified"))
      (node (ref "CN2") (pin "15") (pinfunction "15_15") (pintype "unspecified"))
    )
    (net (code "72") (name "WSTK_P13") (class "Default")
      (node (ref "CN18") (pin "16") (pinfunction "16_16") (pintype "unspecified"))
      (node (ref "CN2") (pin "16") (pinfunction "16_16") (pintype "unspecified"))
    )
    (net (code "73") (name "WSTK_P41") (class "Default")
      (node (ref "CN17") (pin "8") (pinfunction "8_8") (pintype "unspecified"))
      (node (ref "R7") (pin "2") (pinfunction "2_2") (pintype "input"))
    )
    (net (code "74") (name "WSTK_P43") (class "Default")
      (node (ref "CN17") (pin "10") (pinfunction "10_10") (pintype "unspecified"))
      (node (ref "R3") (pin "2") (pinfunction "2_2") (pintype "input"))
      (node (ref "R6") (pin "1") (pinfunction "1_1") (pintype "input"))
    )
    (net (code "75") (name "unconnected-(CN1-Pad1)") (class "Default")
      (node (ref "CN1") (pin "1") (pinfunction "1_1") (pintype "unspecified+no_connect"))
    )
    (net (code "76") (name "unconnected-(CN1-Pad3)") (class "Default")
      (node (ref "CN1") (pin "3") (pinfunction "3_3") (pintype "unspecified+no_connect"))
    )
    (net (code "77") (name "unconnected-(CN2-Pad3)") (class "Default")
      (node (ref "CN2") (pin "3") (pinfunction "3_3") (pintype "unspecified+no_connect"))
    )
    (net (code "78") (name "unconnected-(CN2-Pad5)") (class "Default")
      (node (ref "CN2") (pin "5") (pinfunction "5_5") (pintype "unspecified+no_connect"))
    )
    (net (code "79") (name "unconnected-(CN2-Pad12)") (class "Default")
      (node (ref "CN2") (pin "12") (pinfunction "12_12") (pintype "unspecified+no_connect"))
    )
    (net (code "80") (name "unconnected-(CN2-Pad14)") (class "Default")
      (node (ref "CN2") (pin "14") (pinfunction "14_14") (pintype "unspecified+no_connect"))
    )
    (net (code "81") (name "unconnected-(CN2-Pad17)") (class "Default")
      (node (ref "CN2") (pin "17") (pinfunction "17_17") (pintype "unspecified+no_connect"))
    )
    (net (code "82") (name "unconnected-(CN2-Pad18)") (class "Default")
      (node (ref "CN2") (pin "18") (pinfunction "18_18") (pintype "unspecified+no_connect"))
    )
    (net (code "83") (name "unconnected-(CN2-Pad19)") (class "Default")
      (node (ref "CN2") (pin "19") (pinfunction "19_19") (pintype "unspecified+no_connect"))
    )
    (net (code "84") (name "unconnected-(CN2-Pad20)") (class "Default")
      (node (ref "CN2") (pin "20") (pinfunction "20_20") (pintype "unspecified+no_connect"))
    )
    (net (code "85") (name "unconnected-(CN2-Pad21)") (class "Default")
      (node (ref "CN2") (pin "21") (pinfunction "21_21") (pintype "unspecified+no_connect"))
    )
    (net (code "86") (name "unconnected-(CN2-Pad22)") (class "Default")
      (node (ref "CN2") (pin "22") (pinfunction "22_22") (pintype "unspecified+no_connect"))
    )
    (net (code "87") (name "unconnected-(CN2-Pad23)") (class "Default")
      (node (ref "CN2") (pin "23") (pinfunction "23_23") (pintype "unspecified+no_connect"))
    )
    (net (code "88") (name "unconnected-(CN2-Pad24)") (class "Default")
      (node (ref "CN2") (pin "24") (pinfunction "24_24") (pintype "unspecified+no_connect"))
    )
    (net (code "89") (name "unconnected-(CN2-Pad25)") (class "Default")
      (node (ref "CN2") (pin "25") (pinfunction "25_25") (pintype "unspecified+no_connect"))
    )
    (net (code "90") (name "unconnected-(CN2-Pad26)") (class "Default")
      (node (ref "CN2") (pin "26") (pinfunction "26_26") (pintype "unspecified+no_connect"))
    )
    (net (code "91") (name "unconnected-(CN2-Pad27)") (class "Default")
      (node (ref "CN2") (pin "27") (pinfunction "27_27") (pintype "unspecified+no_connect"))
    )
    (net (code "92") (name "unconnected-(CN2-Pad28)") (class "Default")
      (node (ref "CN2") (pin "28") (pinfunction "28_28") (pintype "unspecified+no_connect"))
    )
    (net (code "93") (name "unconnected-(CN2-Pad29)") (class "Default")
      (node (ref "CN2") (pin "29") (pinfunction "29_29") (pintype "unspecified+no_connect"))
    )
    (net (code "94") (name "unconnected-(CN2-Pad30)") (class "Default")
      (node (ref "CN2") (pin "30") (pinfunction "30_30") (pintype "unspecified+no_connect"))
    )
    (net (code "95") (name "unconnected-(CN2-Pad31)") (class "Default")
      (node (ref "CN2") (pin "31") (pinfunction "31_31") (pintype "unspecified+no_connect"))
    )
    (net (code "96") (name "unconnected-(CN2-Pad32)") (class "Default")
      (node (ref "CN2") (pin "32") (pinfunction "32_32") (pintype "unspecified+no_connect"))
    )
    (net (code "97") (name "unconnected-(CN2-Pad33)") (class "Default")
      (node (ref "CN2") (pin "33") (pinfunction "33_33") (pintype "unspecified+no_connect"))
    )
    (net (code "98") (name "unconnected-(CN2-Pad34)") (class "Default")
      (node (ref "CN2") (pin "34") (pinfunction "34_34") (pintype "unspecified+no_connect"))
    )
    (net (code "99") (name "unconnected-(CN2-Pad35)") (class "Default")
      (node (ref "CN2") (pin "35") (pinfunction "35_35") (pintype "unspecified+no_connect"))
    )
    (net (code "100") (name "unconnected-(CN2-Pad36)") (class "Default")
      (node (ref "CN2") (pin "36") (pinfunction "36_36") (pintype "unspecified+no_connect"))
    )
    (net (code "101") (name "unconnected-(CN2-Pad37)") (class "Default")
      (node (ref "CN2") (pin "37") (pinfunction "37_37") (pintype "unspecified+no_connect"))
    )
    (net (code "102") (name "unconnected-(CN2-Pad38)") (class "Default")
      (node (ref "CN2") (pin "38") (pinfunction "38_38") (pintype "unspecified+no_connect"))
    )
    (net (code "103") (name "unconnected-(CN2-Pad40)") (class "Default")
      (node (ref "CN2") (pin "40") (pinfunction "40_40") (pintype "unspecified+no_connect"))
    )
    (net (code "104") (name "unconnected-(CN3-Pad1)") (class "Default")
      (node (ref "CN3") (pin "1") (pinfunction "1_1") (pintype "unspecified+no_connect"))
    )
    (net (code "105") (name "unconnected-(CN3-Pad3)") (class "Default")
      (node (ref "CN3") (pin "3") (pinfunction "3_3") (pintype "unspecified+no_connect"))
    )
    (net (code "106") (name "unconnected-(CN17-Pad3)") (class "Default")
      (node (ref "CN17") (pin "3") (pinfunction "3_3") (pintype "unspecified+no_connect"))
    )
    (net (code "107") (name "unconnected-(CN17-Pad4)") (class "Default")
      (node (ref "CN17") (pin "4") (pinfunction "4_4") (pintype "unspecified+no_connect"))
    )
    (net (code "108") (name "unconnected-(CN17-Pad5)") (class "Default")
      (node (ref "CN17") (pin "5") (pinfunction "5_5") (pintype "unspecified+no_connect"))
    )
    (net (code "109") (name "unconnected-(CN17-Pad6)") (class "Default")
      (node (ref "CN17") (pin "6") (pinfunction "6_6") (pintype "unspecified+no_connect"))
    )
    (net (code "110") (name "unconnected-(CN17-Pad7)") (class "Default")
      (node (ref "CN17") (pin "7") (pinfunction "7_7") (pintype "unspecified+no_connect"))
    )
    (net (code "111") (name "unconnected-(CN17-Pad9)") (class "Default")
      (node (ref "CN17") (pin "9") (pinfunction "9_9") (pintype "unspecified+no_connect"))
    )
    (net (code "112") (name "unconnected-(CN17-Pad11)") (class "Default")
      (node (ref "CN17") (pin "11") (pinfunction "11_11") (pintype "unspecified+no_connect"))
    )
    (net (code "113") (name "unconnected-(CN17-Pad12)") (class "Default")
      (node (ref "CN17") (pin "12") (pinfunction "12_12") (pintype "unspecified+no_connect"))
    )
    (net (code "114") (name "unconnected-(CN17-Pad27)") (class "Default")
      (node (ref "CN17") (pin "27") (pinfunction "27_27") (pintype "unspecified+no_connect"))
    )
    (net (code "115") (name "unconnected-(CN17-Pad28)") (class "Default")
      (node (ref "CN17") (pin "28") (pinfunction "28_28") (pintype "unspecified+no_connect"))
    )
    (net (code "116") (name "unconnected-(CN17-Pad29)") (class "Default")
      (node (ref "CN17") (pin "29") (pinfunction "29_29") (pintype "unspecified+no_connect"))
    )
    (net (code "117") (name "unconnected-(CN17-Pad30)") (class "Default")
      (node (ref "CN17") (pin "30") (pinfunction "30_30") (pintype "unspecified+no_connect"))
    )
    (net (code "118") (name "unconnected-(CN17-Pad31)") (class "Default")
      (node (ref "CN17") (pin "31") (pinfunction "31_31") (pintype "unspecified+no_connect"))
    )
    (net (code "119") (name "unconnected-(CN17-Pad34)") (class "Default")
      (node (ref "CN17") (pin "34") (pinfunction "34_34") (pintype "unspecified+no_connect"))
    )
    (net (code "120") (name "unconnected-(CN17-Pad35)") (class "Default")
      (node (ref "CN17") (pin "35") (pinfunction "35_35") (pintype "unspecified+no_connect"))
    )
    (net (code "121") (name "unconnected-(CN17-Pad36)") (class "Default")
      (node (ref "CN17") (pin "36") (pinfunction "36_36") (pintype "unspecified+no_connect"))
    )
    (net (code "122") (name "unconnected-(CN17-Pad39)") (class "Default")
      (node (ref "CN17") (pin "39") (pinfunction "39_39") (pintype "unspecified+no_connect"))
    )
    (net (code "123") (name "unconnected-(CN17-Pad40)") (class "Default")
      (node (ref "CN17") (pin "40") (pinfunction "40_40") (pintype "unspecified+no_connect"))
    )
    (net (code "124") (name "unconnected-(CN18-Pad17)") (class "Default")
      (node (ref "CN18") (pin "17") (pinfunction "17_17") (pintype "unspecified+no_connect"))
    )
    (net (code "125") (name "unconnected-(CN18-Pad19)") (class "Default")
      (node (ref "CN18") (pin "19") (pinfunction "19_19") (pintype "unspecified+no_connect"))
    )
    (net (code "126") (name "unconnected-(SW10-Pad3)") (class "Default")
      (node (ref "SW10") (pin "3") (pinfunction "3_3") (pintype "unspecified+no_connect"))
    )
  )
)
